# 3_1_b_organized.net
KiCad netlist of a schematic drawn in EAGLE
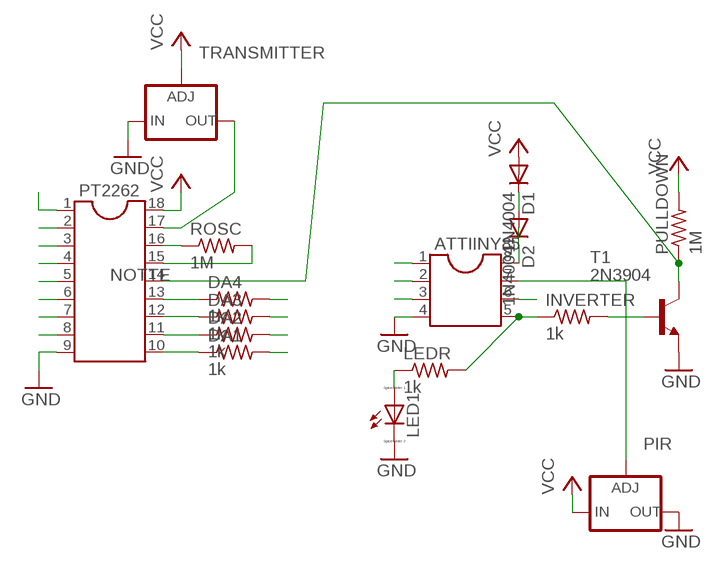
[diagram p0: schematic, sheet 1]

(export (version "E")
  (design (tool "Eeschema 10.0.6"))
  (components
    (comp (ref "ATTIINY85")
      (value "DIL8")
      (footprint "eagle-import:DIL08")
      (libsource (lib "eagle-import") (part "DIL8"))
    )
    (comp (ref "D1")
      (value "1N4004")
      (footprint "eagle-import:DO41-10")
      (libsource (lib "eagle-import") (part "1N4004"))
    )
    (comp (ref "D2")
      (value "1N4004")
      (footprint "eagle-import:DO41-10")
      (libsource (lib "eagle-import") (part "1N4004"))
    )
    (comp (ref "DA1")
      (value "1k")
      (footprint "eagle-import:0207_5V")
      (libsource (lib "eagle-import") (part "R-US_0207/5V"))
    )
    (comp (ref "DA2")
      (value "1k")
      (footprint "eagle-import:0207_5V")
      (libsource (lib "eagle-import") (part "R-US_0207/5V"))
    )
    (comp (ref "DA3")
      (value "1k")
      (footprint "eagle-import:0207_5V")
      (libsource (lib "eagle-import") (part "R-US_0207/5V"))
    )
    (comp (ref "DA4")
      (value "1k")
      (footprint "eagle-import:0207_5V")
      (libsource (lib "eagle-import") (part "R-US_0207/5V"))
    )
    (comp (ref "INVERTER")
      (value "1k")
      (footprint "eagle-import:0207_5V")
      (libsource (lib "eagle-import") (part "R-US_0207/5V"))
    )
    (comp (ref "LED1")
      (value "LED_ELD260")
      (footprint "eagle-import:LED_LD260")
      (libsource (lib "eagle-import") (part "LED_ELD260"))
    )
    (comp (ref "LEDR")
      (value "1k")
      (footprint "eagle-import:0204_5")
      (libsource (lib "eagle-import") (part "R-US_0204/5"))
    )
    (comp (ref "PIR")
      (value "LM337TS")
      (footprint "eagle-import:337TS")
      (libsource (lib "eagle-import") (part "LM337TS"))
    )
    (comp (ref "PT2262")
      (value "DIL18")
      (footprint "eagle-import:DIL18")
      (libsource (lib "eagle-import") (part "DIL18"))
    )
    (comp (ref "PULLDOWN")
      (value "1M")
      (footprint "eagle-import:0207_5V")
      (libsource (lib "eagle-import") (part "R-US_0207/5V"))
    )
    (comp (ref "ROSC")
      (value "1M")
      (footprint "eagle-import:0204_5")
      (libsource (lib "eagle-import") (part "resistor_R-US_0204/5"))
    )
    (comp (ref "T1")
      (value "2N3904")
      (footprint "eagle-import:TO92")
      (libsource (lib "eagle-import") (part "2N3904"))
    )
    (comp (ref "TRANSMITTER")
      (value "LM337TS")
      (footprint "eagle-import:337TS")
      (libsource (lib "eagle-import") (part "LM337TS"))
    )
  )
  (nets
    (net (code "1") (name "/NOTTE") (class "Default")
      (node (ref "PT2262") (pin "14") (pinfunction "14_14") (pintype "passive"))
      (node (ref "PULLDOWN") (pin "1") (pinfunction "1_1") (pintype "passive"))
      (node (ref "T1") (pin "1") (pinfunction "C_1") (pintype "passive"))
    )
    (net (code "2") (name "GND") (class "Default")
      (node (ref "ATTIINY85") (pin "4") (pinfunction "4_4") (pintype "passive"))
      (node (ref "LED1") (pin "K") (pinfunction "C_K") (pintype "passive"))
      (node (ref "PIR") (pin "3") (pinfunction "OUT_3") (pintype "passive"))
      (node (ref "PT2262") (pin "9") (pinfunction "9_9") (pintype "passive"))
      (node (ref "T1") (pin "3") (pinfunction "E_3") (pintype "passive"))
      (node (ref "TRANSMITTER") (pin "2") (pinfunction "IN_2") (pintype "input"))
    )
    (net (code "3") (name "Net-(ATTIINY85-Pad5)") (class "Default")
      (node (ref "ATTIINY85") (pin "5") (pinfunction "5_5") (pintype "passive"))
      (node (ref "INVERTER") (pin "1") (pinfunction "1_1") (pintype "passive"))
      (node (ref "LEDR") (pin "2") (pinfunction "2_2") (pintype "passive"))
    )
    (net (code "4") (name "Net-(ATTIINY85-Pad8)") (class "Default")
      (node (ref "ATTIINY85") (pin "8") (pinfunction "8_8") (pintype "passive"))
      (node (ref "D2") (pin "C") (pinfunction "C_C") (pintype "passive"))
    )
    (net (code "5") (name "Net-(D1-PadC)") (class "Default")
      (node (ref "D1") (pin "C") (pinfunction "C_C") (pintype "passive"))
      (node (ref "D2") (pin "A") (pinfunction "A_A") (pintype "passive"))
    )
    (net (code "6") (name "Net-(DA1-Pad1)") (class "Default")
      (node (ref "DA1") (pin "1") (pinfunction "1_1") (pintype "passive"))
      (node (ref "PT2262") (pin "10") (pinfunction "10_10") (pintype "passive"))
    )
    (net (code "7") (name "Net-(DA2-Pad1)") (class "Default")
      (node (ref "DA2") (pin "1") (pinfunction "1_1") (pintype "passive"))
      (node (ref "PT2262") (pin "11") (pinfunction "11_11") (pintype "passive"))
    )
    (net (code "8") (name "Net-(DA3-Pad1)") (class "Default")
      (node (ref "DA3") (pin "1") (pinfunction "1_1") (pintype "passive"))
      (node (ref "PT2262") (pin "12") (pinfunction "12_12") (pintype "passive"))
    )
    (net (code "9") (name "Net-(DA4-Pad1)") (class "Default")
      (node (ref "DA4") (pin "1") (pinfunction "1_1") (pintype "passive"))
      (node (ref "PT2262") (pin "13") (pinfunction "13_13") (pintype "passive"))
    )
    (net (code "10") (name "Net-(LED1-PadA)") (class "Default")
      (node (ref "LED1") (pin "A") (pinfunction "A_A") (pintype "passive"))
      (node (ref "LEDR") (pin "1") (pinfunction "1_1") (pintype "passive"))
    )
    (net (code "11") (name "Net-(PIR-ADJ)") (class "Default")
      (node (ref "ATTIINY85") (pin "7") (pinfunction "7_7") (pintype "passive"))
      (node (ref "PIR") (pin "1") (pinfunction "ADJ_1") (pintype "input"))
    )
    (net (code "12") (name "Net-(PT2262-Pad15)") (class "Default")
      (node (ref "PT2262") (pin "15") (pinfunction "15_15") (pintype "passive"))
      (node (ref "ROSC") (pin "2") (pinfunction "2_2") (pintype "passive"))
    )
    (net (code "13") (name "Net-(PT2262-Pad16)") (class "Default")
      (node (ref "PT2262") (pin "16") (pinfunction "16_16") (pintype "passive"))
      (node (ref "ROSC") (pin "1") (pinfunction "1_1") (pintype "passive"))
    )
    (net (code "14") (name "Net-(T1-B)") (class "Default")
      (node (ref "INVERTER") (pin "2") (pinfunction "2_2") (pintype "passive"))
      (node (ref "T1") (pin "2") (pinfunction "B_2") (pintype "passive"))
    )
    (net (code "15") (name "Net-(TRANSMITTER-OUT)") (class "Default")
      (node (ref "PT2262") (pin "17") (pinfunction "17_17") (pintype "passive"))
      (node (ref "TRANSMITTER") (pin "3") (pinfunction "OUT_3") (pintype "passive"))
    )
    (net (code "16") (name "VCC") (class "Default")
      (node (ref "D1") (pin "A") (pinfunction "A_A") (pintype "passive"))
      (node (ref "PIR") (pin "2") (pinfunction "IN_2") (pintype "input"))
      (node (ref "PT2262") (pin "18") (pinfunction "18_18") (pintype "passive"))
      (node (ref "PULLDOWN") (pin "2") (pinfunction "2_2") (pintype "passive"))
      (node (ref "TRANSMITTER") (pin "1") (pinfunction "ADJ_1") (pintype "input"))
    )
    (net (code "17") (name "unconnected-(ATTIINY85-Pad1)") (class "Default")
      (node (ref "ATTIINY85") (pin "1") (pinfunction "1_1") (pintype "passive"))
    )
    (net (code "18") (name "unconnected-(ATTIINY85-Pad2)") (class "Default")
      (node (ref "ATTIINY85") (pin "2") (pinfunction "2_2") (pintype "passive"))
    )
    (net (code "19") (name "unconnected-(ATTIINY85-Pad3)") (class "Default")
      (node (ref "ATTIINY85") (pin "3") (pinfunction "3_3") (pintype "passive"))
    )
    (net (code "20") (name "unconnected-(ATTIINY85-Pad6)") (class "Default")
      (node (ref "ATTIINY85") (pin "6") (pinfunction "6_6") (pintype "passive"))
    )
    (net (code "21") (name "unconnected-(DA1-Pad2)") (class "Default")
      (node (ref "DA1") (pin "2") (pinfunction "2_2") (pintype "passive"))
    )
    (net (code "22") (name "unconnected-(DA2-Pad2)") (class "Default")
      (node (ref "DA2") (pin "2") (pinfunction "2_2") (pintype "passive"))
    )
    (net (code "23") (name "unconnected-(DA3-Pad2)") (class "Default")
      (node (ref "DA3") (pin "2") (pinfunction "2_2") (pintype "passive"))
    )
    (net (code "24") (name "unconnected-(DA4-Pad2)") (class "Default")
      (node (ref "DA4") (pin "2") (pinfunction "2_2") (pintype "passive"))
    )
    (net (code "25") (name "unconnected-(PT2262-Pad1)") (class "Default")
      (node (ref "PT2262") (pin "1") (pinfunction "1_1") (pintype "passive"))
    )
    (net (code "26") (name "unconnected-(PT2262-Pad2)") (class "Default")
      (node (ref "PT2262") (pin "2") (pinfunction "2_2") (pintype "passive"))
    )
    (net (code "27") (name "unconnected-(PT2262-Pad3)") (class "Default")
      (node (ref "PT2262") (pin "3") (pinfunction "3_3") (pintype "passive"))
    )
    (net (code "28") (name "unconnected-(PT2262-Pad4)") (class "Default")
      (node (ref "PT2262") (pin "4") (pinfunction "4_4") (pintype "passive"))
    )
    (net (code "29") (name "unconnected-(PT2262-Pad5)") (class "Default")
      (node (ref "PT2262") (pin "5") (pinfunction "5_5") (pintype "passive"))
    )
    (net (code "30") (name "unconnected-(PT2262-Pad6)") (class "Default")
      (node (ref "PT2262") (pin "6") (pinfunction "6_6") (pintype "passive"))
    )
    (net (code "31") (name "unconnected-(PT2262-Pad7)") (class "Default")
      (node (ref "PT2262") (pin "7") (pinfunction "7_7") (pintype "passive"))
    )
    (net (code "32") (name "unconnected-(PT2262-Pad8)") (class "Default")
      (node (ref "PT2262") (pin "8") (pinfunction "8_8") (pintype "passive"))
    )
  )
)
